# stm32_encoderXY_imu.net
KiCad netlist of a schematic drawn in EAGLE
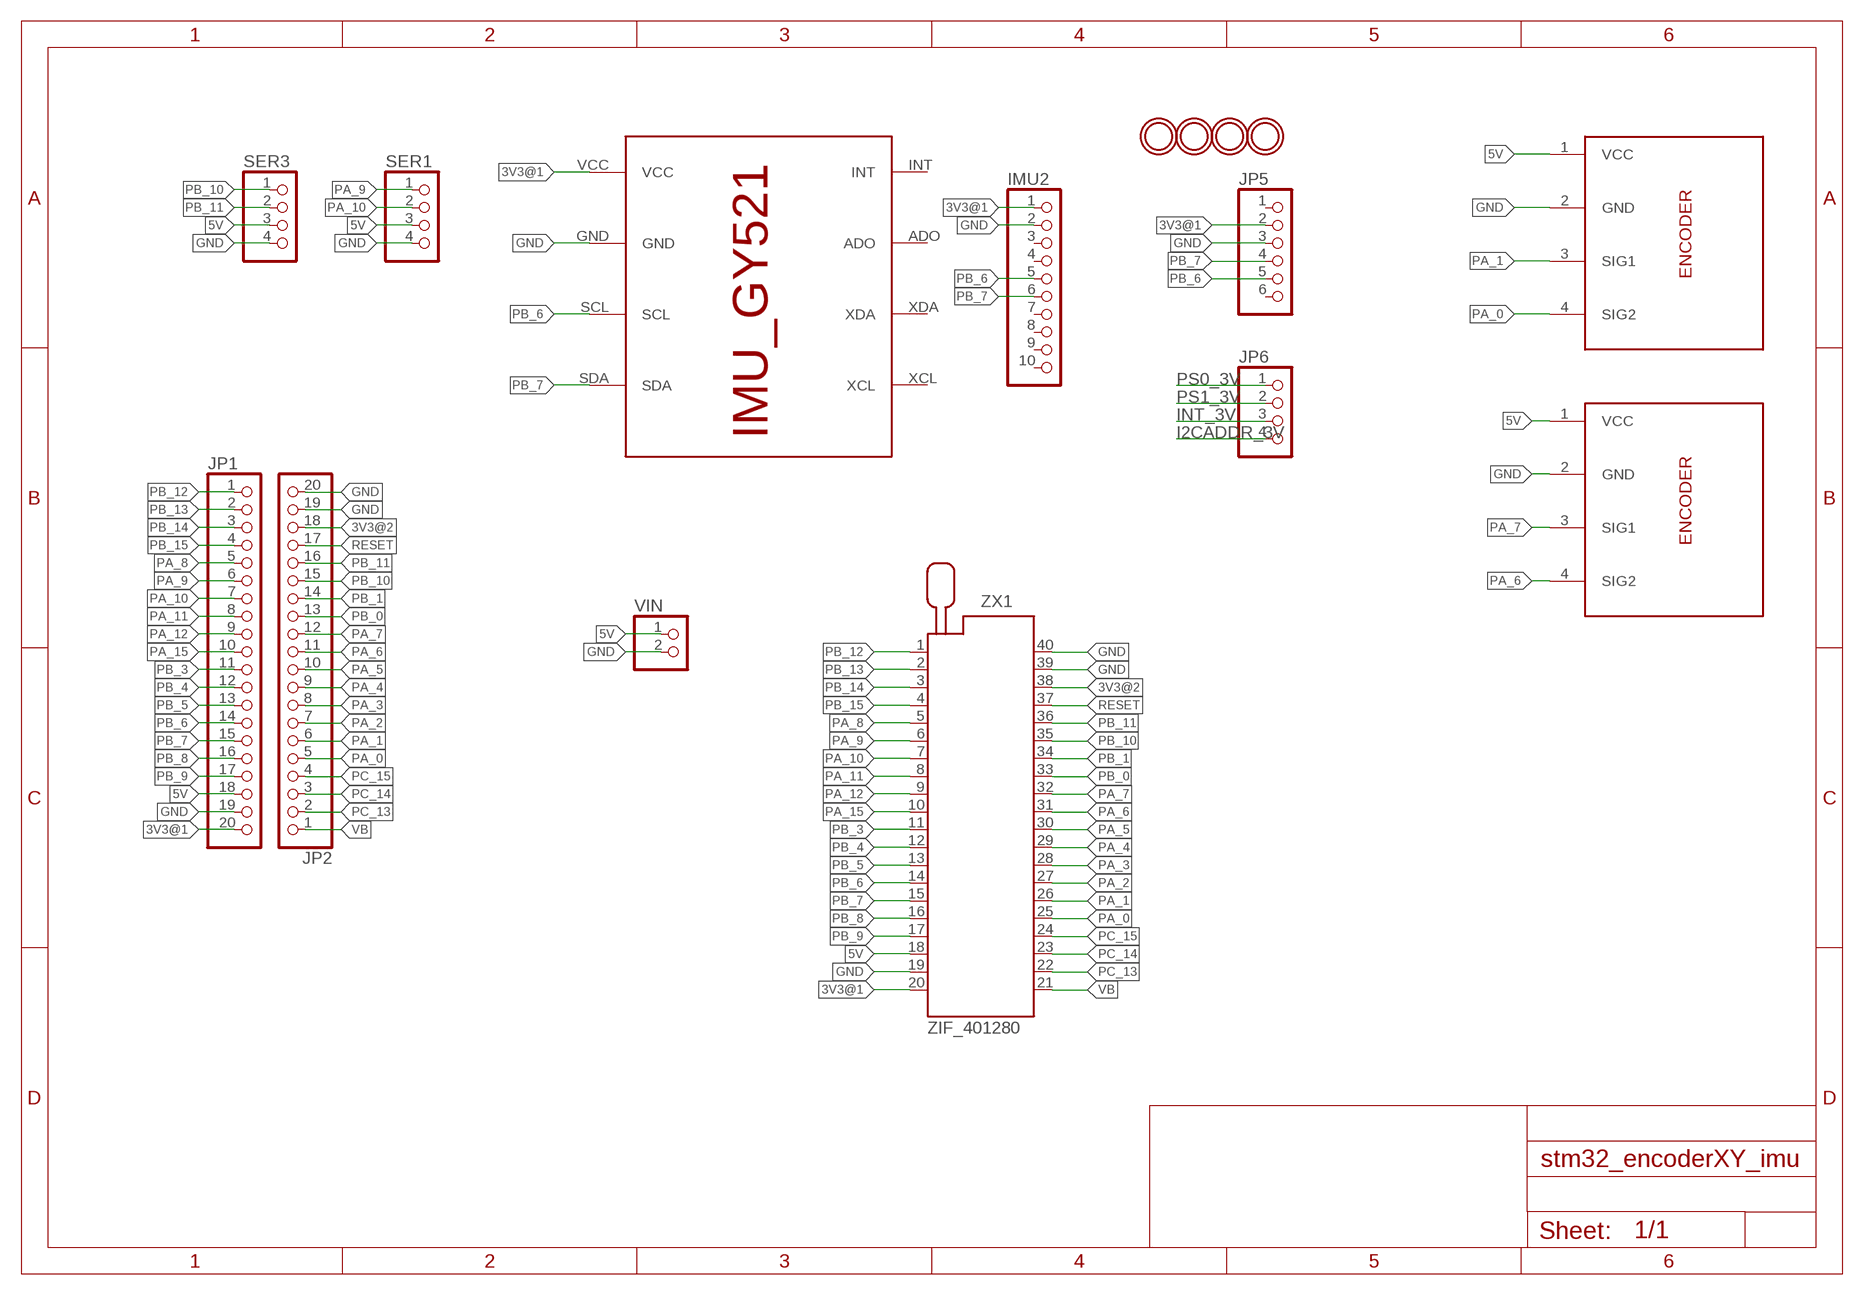
[diagram p0: schematic, sheet 1]

(export (version "E")
  (design (tool "Eeschema 10.0.6"))
  (components
    (comp (ref "ENC1")
      (value "ENC_Y")
      (footprint "eagle-import:1X04_DATA")
      (libsource (lib "eagle-import") (part "ENCODER"))
    )
    (comp (ref "ENC2")
      (value "ENC_X")
      (footprint "eagle-import:1X04_DATA")
      (libsource (lib "eagle-import") (part "ENCODER"))
    )
    (comp (ref "IMU1")
      (value "IMU_ROBOCON_GY521")
      (footprint "eagle-import:IMU_GY521")
      (libsource (lib "eagle-import") (part "IMU_ROBOCON_GY521"))
    )
    (comp (ref "IMU2")
      (value "PINHD-1X10")
      (footprint "eagle-import:1X10")
      (libsource (lib "eagle-import") (part "PINHD-1X10"))
    )
    (comp (ref "JP1")
      (value "PINHD-1X20")
      (footprint "eagle-import:1X20")
      (libsource (lib "eagle-import") (part "PINHD-1X20"))
    )
    (comp (ref "JP2")
      (value "PINHD-1X20")
      (footprint "eagle-import:1X20")
      (libsource (lib "eagle-import") (part "PINHD-1X20"))
    )
    (comp (ref "JP5")
      (value "HEADER-1X676MIL")
      (footprint "eagle-import:1X06_ROUND_76")
      (libsource (lib "eagle-import") (part "HEADER-1X676MIL"))
    )
    (comp (ref "JP6")
      (value "HEADER-1X476MIL")
      (footprint "eagle-import:1X04_ROUND_76")
      (libsource (lib "eagle-import") (part "HEADER-1X476MIL"))
    )
    (comp (ref "SER1")
      (value "PINHD-4_DATA")
      (footprint "eagle-import:1X04_DATA")
      (libsource (lib "eagle-import") (part "PINHD-4_DATA"))
    )
    (comp (ref "SER3")
      (value "PINHD-4_DATA")
      (footprint "eagle-import:1X04_DATA")
      (libsource (lib "eagle-import") (part "PINHD-4_DATA"))
    )
    (comp (ref "U$4")
      (value "MOUNTINGHOLE2.5_THICK")
      (footprint "eagle-import:MOUNTINGHOLE_2.5_PLATED_THICK")
      (libsource (lib "eagle-import") (part "MOUNTINGHOLE2.5_THICK"))
    )
    (comp (ref "U$5")
      (value "MOUNTINGHOLE2.5_THICK")
      (footprint "eagle-import:MOUNTINGHOLE_2.5_PLATED_THICK")
      (libsource (lib "eagle-import") (part "MOUNTINGHOLE2.5_THICK"))
    )
    (comp (ref "U$6")
      (value "MOUNTINGHOLE2.5_THICK")
      (footprint "eagle-import:MOUNTINGHOLE_2.5_PLATED_THICK")
      (libsource (lib "eagle-import") (part "MOUNTINGHOLE2.5_THICK"))
    )
    (comp (ref "U$7")
      (value "MOUNTINGHOLE2.5_THICK")
      (footprint "eagle-import:MOUNTINGHOLE_2.5_PLATED_THICK")
      (libsource (lib "eagle-import") (part "MOUNTINGHOLE2.5_THICK"))
    )
    (comp (ref "VIN")
      (value "PINHD-2_DATA")
      (footprint "eagle-import:1X02_DATA")
      (libsource (lib "eagle-import") (part "PINHD-2_DATA"))
    )
    (comp (ref "ZX1")
      (value "ZIF_401280")
      (footprint "eagle-import:240-1280-00-0602J")
      (libsource (lib "eagle-import") (part "ZIF_401280"))
    )
  )
  (nets
    (net (code "1") (name "/I2CADDR_3V") (class "Default")
      (node (ref "JP6") (pin "4") (pinfunction "4_4") (pintype "passive"))
    )
    (net (code "2") (name "/INT_3V") (class "Default")
      (node (ref "JP6") (pin "3") (pinfunction "3_3") (pintype "passive"))
    )
    (net (code "3") (name "/PS0_3V") (class "Default")
      (node (ref "JP6") (pin "1") (pinfunction "1_1") (pintype "passive"))
    )
    (net (code "4") (name "/PS1_3V") (class "Default")
      (node (ref "JP6") (pin "2") (pinfunction "2_2") (pintype "passive"))
    )
    (net (code "5") (name "3V3@1") (class "Default")
      (node (ref "IMU1") (pin "VCC") (pinfunction "VCC_VCC") (pintype "bidirectional"))
      (node (ref "IMU2") (pin "1") (pinfunction "1_1") (pintype "passive"))
      (node (ref "JP1") (pin "20") (pinfunction "20_20") (pintype "passive"))
      (node (ref "JP5") (pin "2") (pinfunction "2_2") (pintype "passive"))
      (node (ref "ZX1") (pin "20") (pinfunction "20_20") (pintype "passive"))
    )
    (net (code "6") (name "3V3@2") (class "Default")
      (node (ref "JP2") (pin "18") (pinfunction "18_18") (pintype "passive"))
      (node (ref "ZX1") (pin "38") (pinfunction "38_38") (pintype "passive"))
    )
    (net (code "7") (name "5V") (class "Default")
      (node (ref "ENC1") (pin "1") (pinfunction "VCC_1") (pintype "bidirectional"))
      (node (ref "ENC2") (pin "1") (pinfunction "VCC_1") (pintype "bidirectional"))
      (node (ref "JP1") (pin "18") (pinfunction "18_18") (pintype "passive"))
      (node (ref "SER1") (pin "3") (pinfunction "3_3") (pintype "passive"))
      (node (ref "SER3") (pin "3") (pinfunction "3_3") (pintype "passive"))
      (node (ref "VIN") (pin "1") (pinfunction "1_1") (pintype "passive"))
      (node (ref "ZX1") (pin "18") (pinfunction "18_18") (pintype "passive"))
    )
    (net (code "8") (name "GND") (class "Default")
      (node (ref "ENC1") (pin "2") (pinfunction "GND_2") (pintype "bidirectional"))
      (node (ref "ENC2") (pin "2") (pinfunction "GND_2") (pintype "bidirectional"))
      (node (ref "IMU1") (pin "GND") (pinfunction "GND_GND") (pintype "bidirectional"))
      (node (ref "IMU2") (pin "2") (pinfunction "2_2") (pintype "passive"))
      (node (ref "JP1") (pin "19") (pinfunction "19_19") (pintype "passive"))
      (node (ref "JP2") (pin "19") (pinfunction "19_19") (pintype "passive"))
      (node (ref "JP2") (pin "20") (pinfunction "20_20") (pintype "passive"))
      (node (ref "JP5") (pin "3") (pinfunction "3_3") (pintype "passive"))
      (node (ref "SER1") (pin "4") (pinfunction "4_4") (pintype "passive"))
      (node (ref "SER3") (pin "4") (pinfunction "4_4") (pintype "passive"))
      (node (ref "VIN") (pin "2") (pinfunction "2_2") (pintype "passive"))
      (node (ref "ZX1") (pin "19") (pinfunction "19_19") (pintype "passive"))
      (node (ref "ZX1") (pin "39") (pinfunction "39_39") (pintype "passive"))
      (node (ref "ZX1") (pin "40") (pinfunction "40_40") (pintype "passive"))
    )
    (net (code "9") (name "PA_0") (class "Default")
      (node (ref "ENC2") (pin "4") (pinfunction "SIG2_4") (pintype "bidirectional"))
      (node (ref "JP2") (pin "5") (pinfunction "5_5") (pintype "passive"))
      (node (ref "ZX1") (pin "25") (pinfunction "25_25") (pintype "passive"))
    )
    (net (code "10") (name "PA_1") (class "Default")
      (node (ref "ENC2") (pin "3") (pinfunction "SIG1_3") (pintype "bidirectional"))
      (node (ref "JP2") (pin "6") (pinfunction "6_6") (pintype "passive"))
      (node (ref "ZX1") (pin "26") (pinfunction "26_26") (pintype "passive"))
    )
    (net (code "11") (name "PA_2") (class "Default")
      (node (ref "JP2") (pin "7") (pinfunction "7_7") (pintype "passive"))
      (node (ref "ZX1") (pin "27") (pinfunction "27_27") (pintype "passive"))
    )
    (net (code "12") (name "PA_3") (class "Default")
      (node (ref "JP2") (pin "8") (pinfunction "8_8") (pintype "passive"))
      (node (ref "ZX1") (pin "28") (pinfunction "28_28") (pintype "passive"))
    )
    (net (code "13") (name "PA_4") (class "Default")
      (node (ref "JP2") (pin "9") (pinfunction "9_9") (pintype "passive"))
      (node (ref "ZX1") (pin "29") (pinfunction "29_29") (pintype "passive"))
    )
    (net (code "14") (name "PA_5") (class "Default")
      (node (ref "JP2") (pin "10") (pinfunction "10_10") (pintype "passive"))
      (node (ref "ZX1") (pin "30") (pinfunction "30_30") (pintype "passive"))
    )
    (net (code "15") (name "PA_6") (class "Default")
      (node (ref "ENC1") (pin "4") (pinfunction "SIG2_4") (pintype "bidirectional"))
      (node (ref "JP2") (pin "11") (pinfunction "11_11") (pintype "passive"))
      (node (ref "ZX1") (pin "31") (pinfunction "31_31") (pintype "passive"))
    )
    (net (code "16") (name "PA_7") (class "Default")
      (node (ref "ENC1") (pin "3") (pinfunction "SIG1_3") (pintype "bidirectional"))
      (node (ref "JP2") (pin "12") (pinfunction "12_12") (pintype "passive"))
      (node (ref "ZX1") (pin "32") (pinfunction "32_32") (pintype "passive"))
    )
    (net (code "17") (name "PA_8") (class "Default")
      (node (ref "JP1") (pin "5") (pinfunction "5_5") (pintype "passive"))
      (node (ref "ZX1") (pin "5") (pinfunction "5_5") (pintype "passive"))
    )
    (net (code "18") (name "PA_9") (class "Default")
      (node (ref "JP1") (pin "6") (pinfunction "6_6") (pintype "passive"))
      (node (ref "SER1") (pin "1") (pinfunction "1_1") (pintype "passive"))
      (node (ref "ZX1") (pin "6") (pinfunction "6_6") (pintype "passive"))
    )
    (net (code "19") (name "PA_10") (class "Default")
      (node (ref "JP1") (pin "7") (pinfunction "7_7") (pintype "passive"))
      (node (ref "SER1") (pin "2") (pinfunction "2_2") (pintype "passive"))
      (node (ref "ZX1") (pin "7") (pinfunction "7_7") (pintype "passive"))
    )
    (net (code "20") (name "PA_11") (class "Default")
      (node (ref "JP1") (pin "8") (pinfunction "8_8") (pintype "passive"))
      (node (ref "ZX1") (pin "8") (pinfunction "8_8") (pintype "passive"))
    )
    (net (code "21") (name "PA_12") (class "Default")
      (node (ref "JP1") (pin "9") (pinfunction "9_9") (pintype "passive"))
      (node (ref "ZX1") (pin "9") (pinfunction "9_9") (pintype "passive"))
    )
    (net (code "22") (name "PA_15") (class "Default")
      (node (ref "JP1") (pin "10") (pinfunction "10_10") (pintype "passive"))
      (node (ref "ZX1") (pin "10") (pinfunction "10_10") (pintype "passive"))
    )
    (net (code "23") (name "PB_0") (class "Default")
      (node (ref "JP2") (pin "13") (pinfunction "13_13") (pintype "passive"))
      (node (ref "ZX1") (pin "33") (pinfunction "33_33") (pintype "passive"))
    )
    (net (code "24") (name "PB_1") (class "Default")
      (node (ref "JP2") (pin "14") (pinfunction "14_14") (pintype "passive"))
      (node (ref "ZX1") (pin "34") (pinfunction "34_34") (pintype "passive"))
    )
    (net (code "25") (name "PB_3") (class "Default")
      (node (ref "JP1") (pin "11") (pinfunction "11_11") (pintype "passive"))
      (node (ref "ZX1") (pin "11") (pinfunction "11_11") (pintype "passive"))
    )
    (net (code "26") (name "PB_4") (class "Default")
      (node (ref "JP1") (pin "12") (pinfunction "12_12") (pintype "passive"))
      (node (ref "ZX1") (pin "12") (pinfunction "12_12") (pintype "passive"))
    )
    (net (code "27") (name "PB_5") (class "Default")
      (node (ref "JP1") (pin "13") (pinfunction "13_13") (pintype "passive"))
      (node (ref "ZX1") (pin "13") (pinfunction "13_13") (pintype "passive"))
    )
    (net (code "28") (name "PB_6") (class "Default")
      (node (ref "IMU1") (pin "SCL") (pinfunction "SCL_SCL") (pintype "bidirectional"))
      (node (ref "IMU2") (pin "5") (pinfunction "5_5") (pintype "passive"))
      (node (ref "JP1") (pin "14") (pinfunction "14_14") (pintype "passive"))
      (node (ref "JP5") (pin "5") (pinfunction "5_5") (pintype "passive"))
      (node (ref "ZX1") (pin "14") (pinfunction "14_14") (pintype "passive"))
    )
    (net (code "29") (name "PB_7") (class "Default")
      (node (ref "IMU1") (pin "SDA") (pinfunction "SDA_SDA") (pintype "bidirectional"))
      (node (ref "IMU2") (pin "6") (pinfunction "6_6") (pintype "passive"))
      (node (ref "JP1") (pin "15") (pinfunction "15_15") (pintype "passive"))
      (node (ref "JP5") (pin "4") (pinfunction "4_4") (pintype "passive"))
      (node (ref "ZX1") (pin "15") (pinfunction "15_15") (pintype "passive"))
    )
    (net (code "30") (name "PB_8") (class "Default")
      (node (ref "JP1") (pin "16") (pinfunction "16_16") (pintype "passive"))
      (node (ref "ZX1") (pin "16") (pinfunction "16_16") (pintype "passive"))
    )
    (net (code "31") (name "PB_9") (class "Default")
      (node (ref "JP1") (pin "17") (pinfunction "17_17") (pintype "passive"))
      (node (ref "ZX1") (pin "17") (pinfunction "17_17") (pintype "passive"))
    )
    (net (code "32") (name "PB_10") (class "Default")
      (node (ref "JP2") (pin "15") (pinfunction "15_15") (pintype "passive"))
      (node (ref "SER3") (pin "1") (pinfunction "1_1") (pintype "passive"))
      (node (ref "ZX1") (pin "35") (pinfunction "35_35") (pintype "passive"))
    )
    (net (code "33") (name "PB_11") (class "Default")
      (node (ref "JP2") (pin "16") (pinfunction "16_16") (pintype "passive"))
      (node (ref "SER3") (pin "2") (pinfunction "2_2") (pintype "passive"))
      (node (ref "ZX1") (pin "36") (pinfunction "36_36") (pintype "passive"))
    )
    (net (code "34") (name "PB_12") (class "Default")
      (node (ref "JP1") (pin "1") (pinfunction "1_1") (pintype "passive"))
      (node (ref "ZX1") (pin "1") (pinfunction "1_1") (pintype "passive"))
    )
    (net (code "35") (name "PB_13") (class "Default")
      (node (ref "JP1") (pin "2") (pinfunction "2_2") (pintype "passive"))
      (node (ref "ZX1") (pin "2") (pinfunction "2_2") (pintype "passive"))
    )
    (net (code "36") (name "PB_14") (class "Default")
      (node (ref "JP1") (pin "3") (pinfunction "3_3") (pintype "passive"))
      (node (ref "ZX1") (pin "3") (pinfunction "3_3") (pintype "passive"))
    )
    (net (code "37") (name "PB_15") (class "Default")
      (node (ref "JP1") (pin "4") (pinfunction "4_4") (pintype "passive"))
      (node (ref "ZX1") (pin "4") (pinfunction "4_4") (pintype "passive"))
    )
    (net (code "38") (name "PC_13") (class "Default")
      (node (ref "JP2") (pin "2") (pinfunction "2_2") (pintype "passive"))
      (node (ref "ZX1") (pin "22") (pinfunction "22_22") (pintype "passive"))
    )
    (net (code "39") (name "PC_14") (class "Default")
      (node (ref "JP2") (pin "3") (pinfunction "3_3") (pintype "passive"))
      (node (ref "ZX1") (pin "23") (pinfunction "23_23") (pintype "passive"))
    )
    (net (code "40") (name "PC_15") (class "Default")
      (node (ref "JP2") (pin "4") (pinfunction "4_4") (pintype "passive"))
      (node (ref "ZX1") (pin "24") (pinfunction "24_24") (pintype "passive"))
    )
    (net (code "41") (name "RESET") (class "Default")
      (node (ref "JP2") (pin "17") (pinfunction "17_17") (pintype "passive"))
      (node (ref "ZX1") (pin "37") (pinfunction "37_37") (pintype "passive"))
    )
    (net (code "42") (name "VB") (class "Default")
      (node (ref "JP2") (pin "1") (pinfunction "1_1") (pintype "passive"))
      (node (ref "ZX1") (pin "21") (pinfunction "21_21") (pintype "passive"))
    )
    (net (code "43") (name "unconnected-(IMU1-PadADO)") (class "Default")
      (node (ref "IMU1") (pin "ADO") (pinfunction "ADO_ADO") (pintype "bidirectional"))
    )
    (net (code "44") (name "unconnected-(IMU1-PadINT)") (class "Default")
      (node (ref "IMU1") (pin "INT") (pinfunction "INT_INT") (pintype "bidirectional"))
    )
    (net (code "45") (name "unconnected-(IMU1-PadXCL)") (class "Default")
      (node (ref "IMU1") (pin "XCL") (pinfunction "XCL_XCL") (pintype "bidirectional"))
    )
    (net (code "46") (name "unconnected-(IMU1-PadXDA)") (class "Default")
      (node (ref "IMU1") (pin "XDA") (pinfunction "XDA_XDA") (pintype "bidirectional"))
    )
    (net (code "47") (name "unconnected-(IMU2-Pad3)") (class "Default")
      (node (ref "IMU2") (pin "3") (pinfunction "3_3") (pintype "passive"))
    )
    (net (code "48") (name "unconnected-(IMU2-Pad4)") (class "Default")
      (node (ref "IMU2") (pin "4") (pinfunction "4_4") (pintype "passive"))
    )
    (net (code "49") (name "unconnected-(IMU2-Pad7)") (class "Default")
      (node (ref "IMU2") (pin "7") (pinfunction "7_7") (pintype "passive"))
    )
    (net (code "50") (name "unconnected-(IMU2-Pad8)") (class "Default")
      (node (ref "IMU2") (pin "8") (pinfunction "8_8") (pintype "passive"))
    )
    (net (code "51") (name "unconnected-(IMU2-Pad9)") (class "Default")
      (node (ref "IMU2") (pin "9") (pinfunction "9_9") (pintype "passive"))
    )
    (net (code "52") (name "unconnected-(IMU2-Pad10)") (class "Default")
      (node (ref "IMU2") (pin "10") (pinfunction "10_10") (pintype "passive"))
    )
    (net (code "53") (name "unconnected-(JP5-Pad1)") (class "Default")
      (node (ref "JP5") (pin "1") (pinfunction "1_1") (pintype "passive"))
    )
    (net (code "54") (name "unconnected-(JP5-Pad6)") (class "Default")
      (node (ref "JP5") (pin "6") (pinfunction "6_6") (pintype "passive"))
    )
  )
)
